# MainBoard.net
KiCad netlist of a schematic drawn in Altium Designer
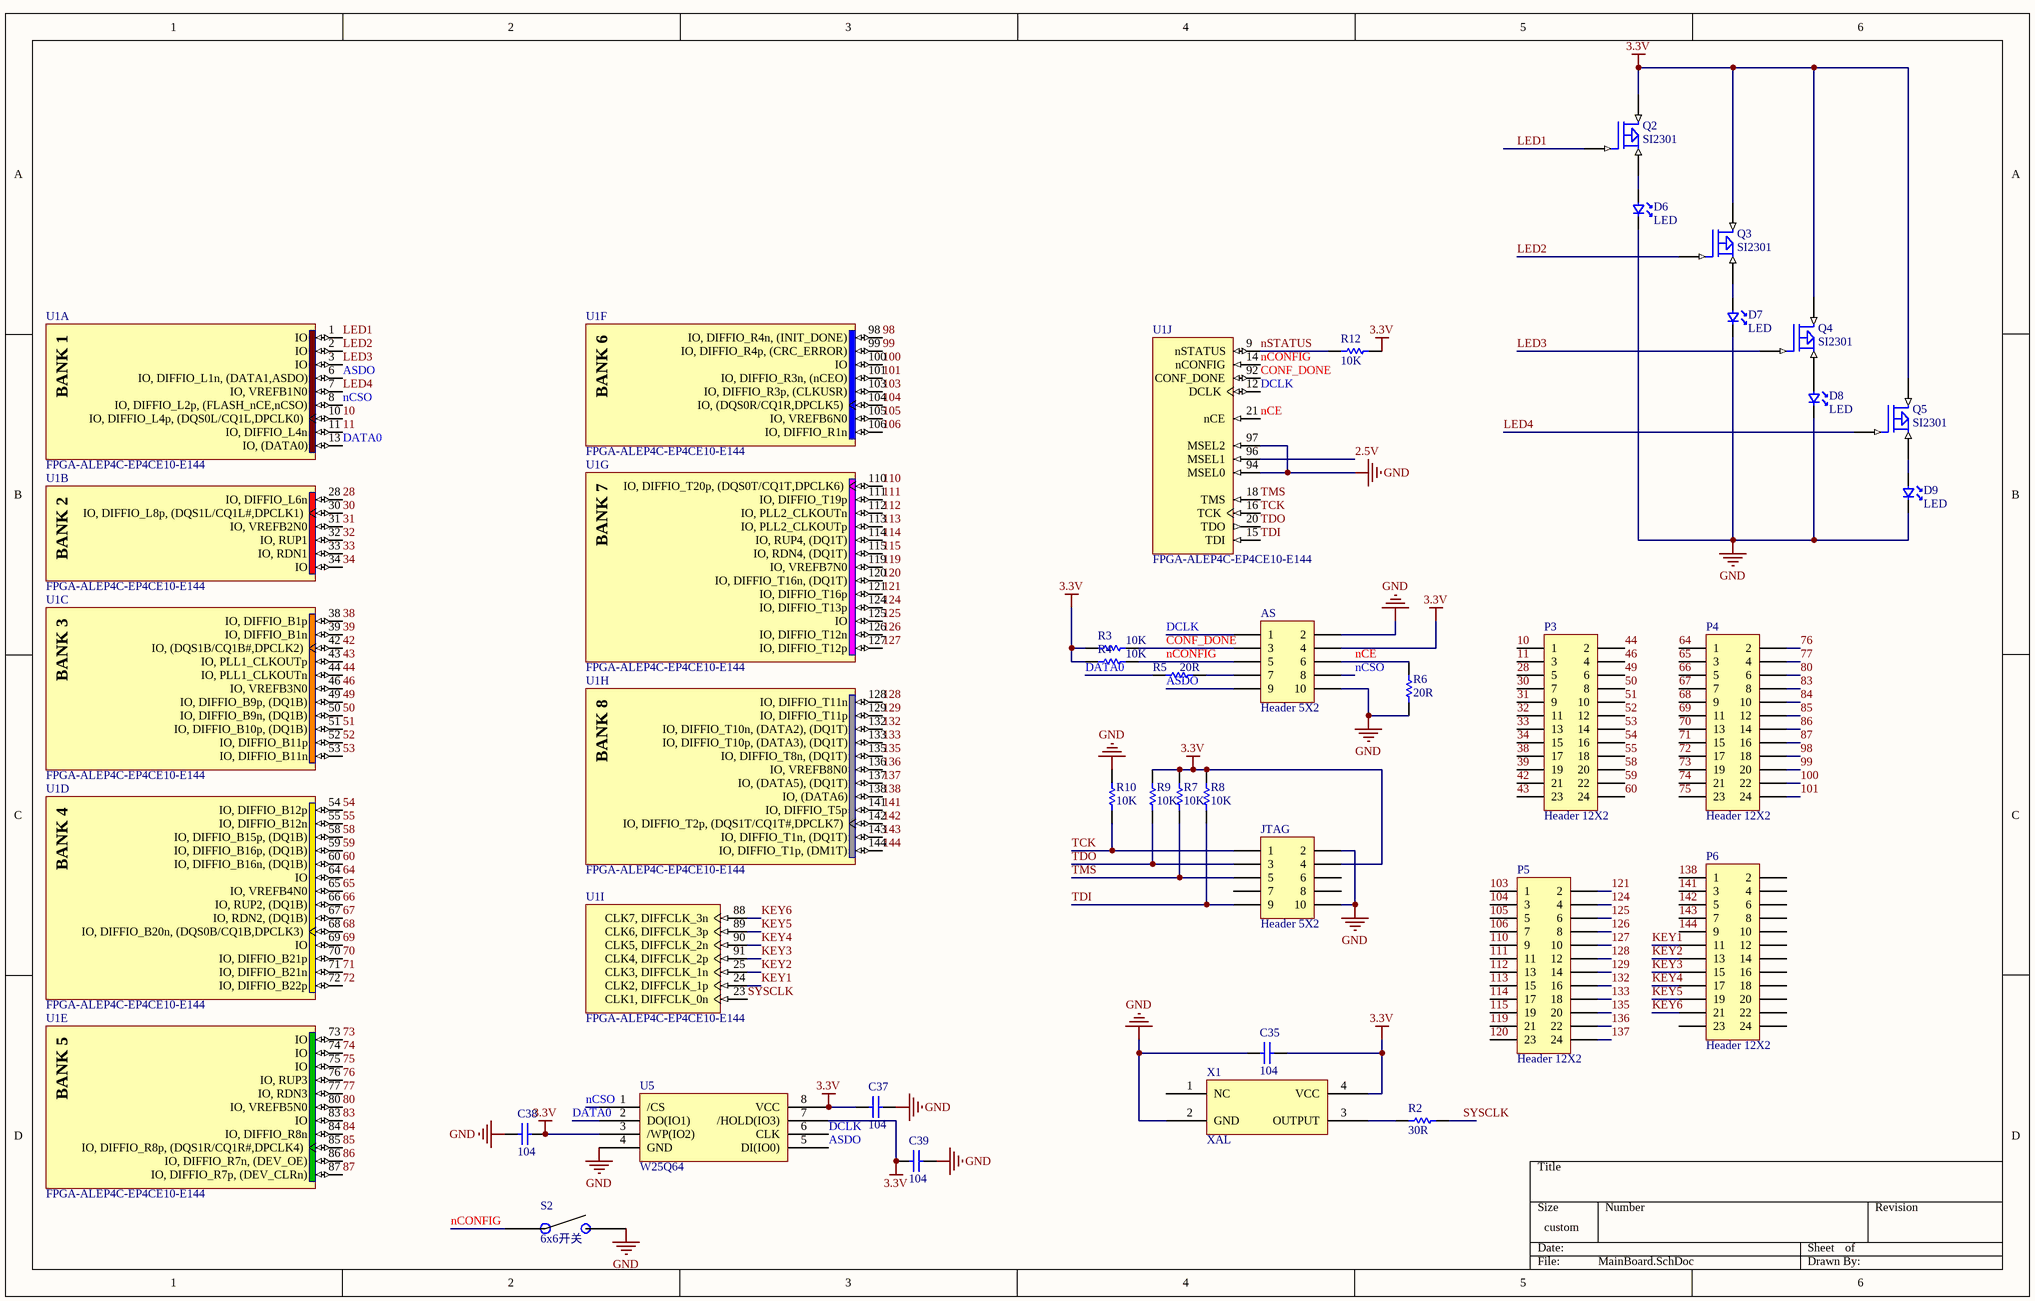
[diagram p0: MainBoard.SchDoc]

(export (version "E")
  (design (tool "Eeschema 10.0.6"))
  (components
    (comp (ref "AS")
      (value "Header 5X2")
      (footprint "HDR2X5")
      (description "Header, 5-Pin, Dual row")
      (fields (field (name "PUBLISHER") "Altium Limited"))
      (libsource (lib "Miscellaneous Connectors") (part "Header 5X2"))
    )
    (comp (ref "C35") (value "104") (footprint "0805") (libsource (lib "Schlib1") (part "Cap")))
    (comp (ref "C37") (value "104") (footprint "0805") (libsource (lib "Schlib1") (part "Cap")))
    (comp (ref "C38") (value "104") (footprint "0805") (libsource (lib "Schlib1") (part "Cap")))
    (comp (ref "C39") (value "104") (footprint "0805") (libsource (lib "Schlib1") (part "Cap")))
    (comp (ref "D6") (value "LED") (footprint "0805_s") (libsource (lib "Schlib1") (part "LED")))
    (comp (ref "D7") (value "LED") (footprint "0805_s") (libsource (lib "Schlib1") (part "LED")))
    (comp (ref "D8") (value "LED") (footprint "0805_s") (libsource (lib "Schlib1") (part "LED")))
    (comp (ref "D9") (value "LED") (footprint "0805_s") (libsource (lib "Schlib1") (part "LED")))
    (comp (ref "JTAG")
      (value "Header 5X2")
      (footprint "HDR2X5")
      (description "Header, 5-Pin, Dual row")
      (fields (field (name "PUBLISHER") "Altium Limited"))
      (libsource (lib "Miscellaneous Connectors") (part "Header 5X2"))
    )
    (comp (ref "P3")
      (value "Header 12X2")
      (footprint "HDR2X12")
      (description "Header, 12-Pin, Dual row")
      (fields (field (name "PUBLISHER") "Altium Limited"))
      (libsource (lib "Miscellaneous Connectors") (part "Header 12X2"))
    )
    (comp (ref "P4")
      (value "Header 12X2")
      (footprint "HDR2X12")
      (description "Header, 12-Pin, Dual row")
      (fields (field (name "PUBLISHER") "Altium Limited"))
      (libsource (lib "Miscellaneous Connectors") (part "Header 12X2"))
    )
    (comp (ref "P5")
      (value "Header 12X2")
      (footprint "HDR2X12")
      (description "Header, 12-Pin, Dual row")
      (fields (field (name "PUBLISHER") "Altium Limited"))
      (libsource (lib "Miscellaneous Connectors") (part "Header 12X2"))
    )
    (comp (ref "P6")
      (value "Header 12X2")
      (footprint "HDR2X12")
      (description "Header, 12-Pin, Dual row")
      (fields (field (name "PUBLISHER") "Altium Limited"))
      (libsource (lib "Miscellaneous Connectors") (part "Header 12X2"))
    )
    (comp (ref "Q2") (value "SI2301") (footprint "SOT-23") (libsource (lib "Schlib1") (part "SI2301")))
    (comp (ref "Q3") (value "SI2301") (footprint "SOT-23") (libsource (lib "Schlib1") (part "SI2301")))
    (comp (ref "Q4") (value "SI2301") (footprint "SOT-23") (libsource (lib "Schlib1") (part "SI2301")))
    (comp (ref "Q5") (value "SI2301") (footprint "SOT-23") (libsource (lib "Schlib1") (part "SI2301")))
    (comp (ref "R2") (value "30R") (footprint "0805") (libsource (lib "Schlib1") (part "Res")))
    (comp (ref "R3") (value "10K") (footprint "0805") (libsource (lib "Schlib1") (part "Res")))
    (comp (ref "R4") (value "10K") (footprint "0805") (libsource (lib "Schlib1") (part "Res")))
    (comp (ref "R5") (value "20R") (footprint "0805") (libsource (lib "Schlib1") (part "Res")))
    (comp (ref "R6") (value "20R") (footprint "0805") (libsource (lib "Schlib1") (part "Res")))
    (comp (ref "R7") (value "10K") (footprint "0805") (libsource (lib "Schlib1") (part "Res")))
    (comp (ref "R8") (value "10K") (footprint "0805") (libsource (lib "Schlib1") (part "Res")))
    (comp (ref "R9") (value "10K") (footprint "0805") (libsource (lib "Schlib1") (part "Res")))
    (comp (ref "R10") (value "10K") (footprint "0805") (libsource (lib "Schlib1") (part "Res")))
    (comp (ref "R12") (value "10K") (footprint "0805") (libsource (lib "Schlib1") (part "Res")))
    (comp (ref "S2") (value "6x6开关") (footprint "AN66") (libsource (lib "Schlib1") (part "6x6开关")))
    (comp (ref "U1")
      (value "FPGA-ALEP4C-EP4CE10-E144")
      (footprint "EQFP144_A-165_D2-54_L")
      (libsource (lib "Schlib1") (part "FPGA-ALEP4C-EP4CE10-E144"))
    )
    (comp (ref "U5")
      (value "W25Q64")
      (footprint "LC-SOIC-8_150mil")
      (libsource (lib "Schlib1") (part "W25Q64"))
    )
    (comp (ref "X1") (value "XAL") (footprint "XAL-SMD-3225_4P") (libsource (lib "Schlib1") (part "XAL")))
  )
  (nets
    (net (code "1") (name "/2.5V") (class "Default")
      (node (ref "U1") (pin "96") (pinfunction "MSEL1_96") (pintype "input"))
    )
    (net (code "2") (name "/10") (class "Default")
      (node (ref "P3") (pin "1") (pinfunction "1_1") (pintype "passive"))
      (node (ref "U1") (pin "10") (pinfunction "IO,_DIFFIO_L4p,_(DQS0L/CQ1L,DPCLK0)_10") (pintype "bidirectional"))
    )
    (net (code "3") (name "/11") (class "Default")
      (node (ref "P3") (pin "3") (pinfunction "3_3") (pintype "passive"))
      (node (ref "U1") (pin "11") (pinfunction "IO,_DIFFIO_L4n_11") (pintype "bidirectional"))
    )
    (net (code "4") (name "/28") (class "Default")
      (node (ref "P3") (pin "5") (pinfunction "5_5") (pintype "passive"))
      (node (ref "U1") (pin "28") (pinfunction "IO,_DIFFIO_L6n_28") (pintype "bidirectional"))
    )
    (net (code "5") (name "/30") (class "Default")
      (node (ref "P3") (pin "7") (pinfunction "7_7") (pintype "passive"))
      (node (ref "U1") (pin "30") (pinfunction "IO,_DIFFIO_L8p,_(DQS1L/CQ1L#,DPCLK1)_30") (pintype "bidirectional"))
    )
    (net (code "6") (name "/31") (class "Default")
      (node (ref "P3") (pin "9") (pinfunction "9_9") (pintype "passive"))
      (node (ref "U1") (pin "31") (pinfunction "IO,_VREFB2N0_31") (pintype "bidirectional"))
    )
    (net (code "7") (name "/32") (class "Default")
      (node (ref "P3") (pin "11") (pinfunction "11_11") (pintype "passive"))
      (node (ref "U1") (pin "32") (pinfunction "IO,_RUP1_32") (pintype "bidirectional"))
    )
    (net (code "8") (name "/33") (class "Default")
      (node (ref "P3") (pin "13") (pinfunction "13_13") (pintype "passive"))
      (node (ref "U1") (pin "33") (pinfunction "IO,_RDN1_33") (pintype "bidirectional"))
    )
    (net (code "9") (name "/34") (class "Default")
      (node (ref "P3") (pin "15") (pinfunction "15_15") (pintype "passive"))
      (node (ref "U1") (pin "34") (pinfunction "IO_34") (pintype "bidirectional"))
    )
    (net (code "10") (name "/38") (class "Default")
      (node (ref "P3") (pin "17") (pinfunction "17_17") (pintype "passive"))
      (node (ref "U1") (pin "38") (pinfunction "IO,_DIFFIO_B1p_38") (pintype "bidirectional"))
    )
    (net (code "11") (name "/39") (class "Default")
      (node (ref "P3") (pin "19") (pinfunction "19_19") (pintype "passive"))
      (node (ref "U1") (pin "39") (pinfunction "IO,_DIFFIO_B1n_39") (pintype "bidirectional"))
    )
    (net (code "12") (name "/42") (class "Default")
      (node (ref "P3") (pin "21") (pinfunction "21_21") (pintype "passive"))
      (node (ref "U1") (pin "42") (pinfunction "IO,_(DQS1B/CQ1B#,DPCLK2)_42") (pintype "bidirectional"))
    )
    (net (code "13") (name "/43") (class "Default")
      (node (ref "P3") (pin "23") (pinfunction "23_23") (pintype "passive"))
      (node (ref "U1") (pin "43") (pinfunction "IO,_PLL1_CLKOUTp_43") (pintype "bidirectional"))
    )
    (net (code "14") (name "/44") (class "Default")
      (node (ref "P3") (pin "2") (pinfunction "2_2") (pintype "passive"))
      (node (ref "U1") (pin "44") (pinfunction "IO,_PLL1_CLKOUTn_44") (pintype "bidirectional"))
    )
    (net (code "15") (name "/46") (class "Default")
      (node (ref "P3") (pin "4") (pinfunction "4_4") (pintype "passive"))
      (node (ref "U1") (pin "46") (pinfunction "IO,_VREFB3N0_46") (pintype "bidirectional"))
    )
    (net (code "16") (name "/49") (class "Default")
      (node (ref "P3") (pin "6") (pinfunction "6_6") (pintype "passive"))
      (node (ref "U1") (pin "49") (pinfunction "IO,_DIFFIO_B9p,_(DQ1B)_49") (pintype "bidirectional"))
    )
    (net (code "17") (name "/50") (class "Default")
      (node (ref "P3") (pin "8") (pinfunction "8_8") (pintype "passive"))
      (node (ref "U1") (pin "50") (pinfunction "IO,_DIFFIO_B9n,_(DQ1B)_50") (pintype "bidirectional"))
    )
    (net (code "18") (name "/51") (class "Default")
      (node (ref "P3") (pin "10") (pinfunction "10_10") (pintype "passive"))
      (node (ref "U1") (pin "51") (pinfunction "IO,_DIFFIO_B10p,_(DQ1B)_51") (pintype "bidirectional"))
    )
    (net (code "19") (name "/52") (class "Default")
      (node (ref "P3") (pin "12") (pinfunction "12_12") (pintype "passive"))
      (node (ref "U1") (pin "52") (pinfunction "IO,_DIFFIO_B11p_52") (pintype "bidirectional"))
    )
    (net (code "20") (name "/53") (class "Default")
      (node (ref "P3") (pin "14") (pinfunction "14_14") (pintype "passive"))
      (node (ref "U1") (pin "53") (pinfunction "IO,_DIFFIO_B11n_53") (pintype "bidirectional"))
    )
    (net (code "21") (name "/54") (class "Default")
      (node (ref "P3") (pin "16") (pinfunction "16_16") (pintype "passive"))
      (node (ref "U1") (pin "54") (pinfunction "IO,_DIFFIO_B12p_54") (pintype "bidirectional"))
    )
    (net (code "22") (name "/55") (class "Default")
      (node (ref "P3") (pin "18") (pinfunction "18_18") (pintype "passive"))
      (node (ref "U1") (pin "55") (pinfunction "IO,_DIFFIO_B12n_55") (pintype "bidirectional"))
    )
    (net (code "23") (name "/58") (class "Default")
      (node (ref "P3") (pin "20") (pinfunction "20_20") (pintype "passive"))
      (node (ref "U1") (pin "58") (pinfunction "IO,_DIFFIO_B15p,_(DQ1B)_58") (pintype "bidirectional"))
    )
    (net (code "24") (name "/59") (class "Default")
      (node (ref "P3") (pin "22") (pinfunction "22_22") (pintype "passive"))
      (node (ref "U1") (pin "59") (pinfunction "IO,_DIFFIO_B16p,_(DQ1B)_59") (pintype "bidirectional"))
    )
    (net (code "25") (name "/60") (class "Default")
      (node (ref "P3") (pin "24") (pinfunction "24_24") (pintype "passive"))
      (node (ref "U1") (pin "60") (pinfunction "IO,_DIFFIO_B16n,_(DQ1B)_60") (pintype "bidirectional"))
    )
    (net (code "26") (name "/64") (class "Default")
      (node (ref "P4") (pin "1") (pinfunction "1_1") (pintype "passive"))
      (node (ref "U1") (pin "64") (pinfunction "IO_64") (pintype "bidirectional"))
    )
    (net (code "27") (name "/65") (class "Default")
      (node (ref "P4") (pin "3") (pinfunction "3_3") (pintype "passive"))
      (node (ref "U1") (pin "65") (pinfunction "IO,_VREFB4N0_65") (pintype "bidirectional"))
    )
    (net (code "28") (name "/66") (class "Default")
      (node (ref "P4") (pin "5") (pinfunction "5_5") (pintype "passive"))
      (node (ref "U1") (pin "66") (pinfunction "IO,_RUP2,_(DQ1B)_66") (pintype "bidirectional"))
    )
    (net (code "29") (name "/67") (class "Default")
      (node (ref "P4") (pin "7") (pinfunction "7_7") (pintype "passive"))
      (node (ref "U1") (pin "67") (pinfunction "IO,_RDN2,_(DQ1B)_67") (pintype "bidirectional"))
    )
    (net (code "30") (name "/68") (class "Default")
      (node (ref "P4") (pin "9") (pinfunction "9_9") (pintype "passive"))
      (node (ref "U1") (pin "68") (pinfunction "IO,_DIFFIO_B20n,_(DQS0B/CQ1B,DPCLK3)_68") (pintype "bidirectional"))
    )
    (net (code "31") (name "/69") (class "Default")
      (node (ref "P4") (pin "11") (pinfunction "11_11") (pintype "passive"))
      (node (ref "U1") (pin "69") (pinfunction "IO_69") (pintype "bidirectional"))
    )
    (net (code "32") (name "/70") (class "Default")
      (node (ref "P4") (pin "13") (pinfunction "13_13") (pintype "passive"))
      (node (ref "U1") (pin "70") (pinfunction "IO,_DIFFIO_B21p_70") (pintype "bidirectional"))
    )
    (net (code "33") (name "/71") (class "Default")
      (node (ref "P4") (pin "15") (pinfunction "15_15") (pintype "passive"))
      (node (ref "U1") (pin "71") (pinfunction "IO,_DIFFIO_B21n_71") (pintype "bidirectional"))
    )
    (net (code "34") (name "/72") (class "Default")
      (node (ref "P4") (pin "17") (pinfunction "17_17") (pintype "passive"))
      (node (ref "U1") (pin "72") (pinfunction "IO,_DIFFIO_B22p_72") (pintype "bidirectional"))
    )
    (net (code "35") (name "/73") (class "Default")
      (node (ref "P4") (pin "19") (pinfunction "19_19") (pintype "passive"))
      (node (ref "U1") (pin "73") (pinfunction "IO_73") (pintype "bidirectional"))
    )
    (net (code "36") (name "/74") (class "Default")
      (node (ref "P4") (pin "21") (pinfunction "21_21") (pintype "passive"))
      (node (ref "U1") (pin "74") (pinfunction "IO_74") (pintype "bidirectional"))
    )
    (net (code "37") (name "/75") (class "Default")
      (node (ref "P4") (pin "23") (pinfunction "23_23") (pintype "passive"))
      (node (ref "U1") (pin "75") (pinfunction "IO_75") (pintype "bidirectional"))
    )
    (net (code "38") (name "/76") (class "Default")
      (node (ref "P4") (pin "2") (pinfunction "2_2") (pintype "passive"))
      (node (ref "U1") (pin "76") (pinfunction "IO,_RUP3_76") (pintype "bidirectional"))
    )
    (net (code "39") (name "/77") (class "Default")
      (node (ref "P4") (pin "4") (pinfunction "4_4") (pintype "passive"))
      (node (ref "U1") (pin "77") (pinfunction "IO,_RDN3_77") (pintype "bidirectional"))
    )
    (net (code "40") (name "/80") (class "Default")
      (node (ref "P4") (pin "6") (pinfunction "6_6") (pintype "passive"))
      (node (ref "U1") (pin "80") (pinfunction "IO,_VREFB5N0_80") (pintype "bidirectional"))
    )
    (net (code "41") (name "/83") (class "Default")
      (node (ref "P4") (pin "8") (pinfunction "8_8") (pintype "passive"))
      (node (ref "U1") (pin "83") (pinfunction "IO_83") (pintype "bidirectional"))
    )
    (net (code "42") (name "/84") (class "Default")
      (node (ref "P4") (pin "10") (pinfunction "10_10") (pintype "passive"))
      (node (ref "U1") (pin "84") (pinfunction "IO,_DIFFIO_R8n_84") (pintype "bidirectional"))
    )
    (net (code "43") (name "/85") (class "Default")
      (node (ref "P4") (pin "12") (pinfunction "12_12") (pintype "passive"))
      (node (ref "U1") (pin "85") (pinfunction "IO,_DIFFIO_R8p,_(DQS1R/CQ1R#,DPCLK4)_85") (pintype "bidirectional"))
    )
    (net (code "44") (name "/86") (class "Default")
      (node (ref "P4") (pin "14") (pinfunction "14_14") (pintype "passive"))
      (node (ref "U1") (pin "86") (pinfunction "IO,_DIFFIO_R7n,_(DEV_OE)_86") (pintype "bidirectional"))
    )
    (net (code "45") (name "/87") (class "Default")
      (node (ref "P4") (pin "16") (pinfunction "16_16") (pintype "passive"))
      (node (ref "U1") (pin "87") (pinfunction "IO,_DIFFIO_R7p,_(DEV_CLRn)_87") (pintype "bidirectional"))
    )
    (net (code "46") (name "/98") (class "Default")
      (node (ref "P4") (pin "18") (pinfunction "18_18") (pintype "passive"))
      (node (ref "U1") (pin "98") (pinfunction "IO,_DIFFIO_R4n,_(INIT_DONE)_98") (pintype "bidirectional"))
    )
    (net (code "47") (name "/99") (class "Default")
      (node (ref "P4") (pin "20") (pinfunction "20_20") (pintype "passive"))
      (node (ref "U1") (pin "99") (pinfunction "IO,_DIFFIO_R4p,_(CRC_ERROR)_99") (pintype "bidirectional"))
    )
    (net (code "48") (name "/100") (class "Default")
      (node (ref "P4") (pin "22") (pinfunction "22_22") (pintype "passive"))
      (node (ref "U1") (pin "100") (pinfunction "IO_100") (pintype "bidirectional"))
    )
    (net (code "49") (name "/101") (class "Default")
      (node (ref "P4") (pin "24") (pinfunction "24_24") (pintype "passive"))
      (node (ref "U1") (pin "101") (pinfunction "IO,_DIFFIO_R3n,_(nCEO)_101") (pintype "bidirectional"))
    )
    (net (code "50") (name "/103") (class "Default")
      (node (ref "P5") (pin "1") (pinfunction "1_1") (pintype "passive"))
      (node (ref "U1") (pin "103") (pinfunction "IO,_DIFFIO_R3p,_(CLKUSR)_103") (pintype "bidirectional"))
    )
    (net (code "51") (name "/104") (class "Default")
      (node (ref "P5") (pin "3") (pinfunction "3_3") (pintype "passive"))
      (node (ref "U1") (pin "104") (pinfunction "IO,_(DQS0R/CQ1R,DPCLK5)_104") (pintype "bidirectional"))
    )
    (net (code "52") (name "/105") (class "Default")
      (node (ref "P5") (pin "5") (pinfunction "5_5") (pintype "passive"))
      (node (ref "U1") (pin "105") (pinfunction "IO,_VREFB6N0_105") (pintype "bidirectional"))
    )
    (net (code "53") (name "/106") (class "Default")
      (node (ref "P5") (pin "7") (pinfunction "7_7") (pintype "passive"))
      (node (ref "U1") (pin "106") (pinfunction "IO,_DIFFIO_R1n_106") (pintype "bidirectional"))
    )
    (net (code "54") (name "/110") (class "Default")
      (node (ref "P5") (pin "9") (pinfunction "9_9") (pintype "passive"))
      (node (ref "U1") (pin "110") (pinfunction "IO,_DIFFIO_T20p,_(DQS0T/CQ1T,DPCLK6)_110") (pintype "bidirectional"))
    )
    (net (code "55") (name "/111") (class "Default")
      (node (ref "P5") (pin "11") (pinfunction "11_11") (pintype "passive"))
      (node (ref "U1") (pin "111") (pinfunction "IO,_DIFFIO_T19p_111") (pintype "bidirectional"))
    )
    (net (code "56") (name "/112") (class "Default")
      (node (ref "P5") (pin "13") (pinfunction "13_13") (pintype "passive"))
      (node (ref "U1") (pin "112") (pinfunction "IO,_PLL2_CLKOUTn_112") (pintype "bidirectional"))
    )
    (net (code "57") (name "/113") (class "Default")
      (node (ref "P5") (pin "15") (pinfunction "15_15") (pintype "passive"))
      (node (ref "U1") (pin "113") (pinfunction "IO,_PLL2_CLKOUTp_113") (pintype "bidirectional"))
    )
    (net (code "58") (name "/114") (class "Default")
      (node (ref "P5") (pin "17") (pinfunction "17_17") (pintype "passive"))
      (node (ref "U1") (pin "114") (pinfunction "IO,_RUP4,_(DQ1T)_114") (pintype "bidirectional"))
    )
    (net (code "59") (name "/115") (class "Default")
      (node (ref "P5") (pin "19") (pinfunction "19_19") (pintype "passive"))
      (node (ref "U1") (pin "115") (pinfunction "IO,_RDN4,_(DQ1T)_115") (pintype "bidirectional"))
    )
    (net (code "60") (name "/119") (class "Default")
      (node (ref "P5") (pin "21") (pinfunction "21_21") (pintype "passive"))
      (node (ref "U1") (pin "119") (pinfunction "IO,_VREFB7N0_119") (pintype "bidirectional"))
    )
    (net (code "61") (name "/120") (class "Default")
      (node (ref "P5") (pin "23") (pinfunction "23_23") (pintype "passive"))
      (node (ref "U1") (pin "120") (pinfunction "IO,_DIFFIO_T16n,_(DQ1T)_120") (pintype "bidirectional"))
    )
    (net (code "62") (name "/121") (class "Default")
      (node (ref "P5") (pin "2") (pinfunction "2_2") (pintype "passive"))
      (node (ref "U1") (pin "121") (pinfunction "IO,_DIFFIO_T16p_121") (pintype "bidirectional"))
    )
    (net (code "63") (name "/124") (class "Default")
      (node (ref "P5") (pin "4") (pinfunction "4_4") (pintype "passive"))
      (node (ref "U1") (pin "124") (pinfunction "IO,_DIFFIO_T13p_124") (pintype "bidirectional"))
    )
    (net (code "64") (name "/125") (class "Default")
      (node (ref "P5") (pin "6") (pinfunction "6_6") (pintype "passive"))
      (node (ref "U1") (pin "125") (pinfunction "IO_125") (pintype "bidirectional"))
    )
    (net (code "65") (name "/126") (class "Default")
      (node (ref "P5") (pin "8") (pinfunction "8_8") (pintype "passive"))
      (node (ref "U1") (pin "126") (pinfunction "IO,_DIFFIO_T12n_126") (pintype "bidirectional"))
    )
    (net (code "66") (name "/127") (class "Default")
      (node (ref "P5") (pin "10") (pinfunction "10_10") (pintype "passive"))
      (node (ref "U1") (pin "127") (pinfunction "IO,_DIFFIO_T12p_127") (pintype "bidirectional"))
    )
    (net (code "67") (name "/128") (class "Default")
      (node (ref "P5") (pin "12") (pinfunction "12_12") (pintype "passive"))
      (node (ref "U1") (pin "128") (pinfunction "IO,_DIFFIO_T11n_128") (pintype "bidirectional"))
    )
    (net (code "68") (name "/129") (class "Default")
      (node (ref "P5") (pin "14") (pinfunction "14_14") (pintype "passive"))
      (node (ref "U1") (pin "129") (pinfunction "IO,_DIFFIO_T11p_129") (pintype "bidirectional"))
    )
    (net (code "69") (name "/132") (class "Default")
      (node (ref "P5") (pin "16") (pinfunction "16_16") (pintype "passive"))
      (node (ref "U1") (pin "132") (pinfunction "IO,_DIFFIO_T10n,_(DATA2),_(DQ1T)_132") (pintype "bidirectional"))
    )
    (net (code "70") (name "/133") (class "Default")
      (node (ref "P5") (pin "18") (pinfunction "18_18") (pintype "passive"))
      (node (ref "U1") (pin "133") (pinfunction "IO,_DIFFIO_T10p,_(DATA3),_(DQ1T)_133") (pintype "bidirectional"))
    )
    (net (code "71") (name "/135") (class "Default")
      (node (ref "P5") (pin "20") (pinfunction "20_20") (pintype "passive"))
      (node (ref "U1") (pin "135") (pinfunction "IO,_DIFFIO_T8n,_(DQ1T)_135") (pintype "bidirectional"))
    )
    (net (code "72") (name "/136") (class "Default")
      (node (ref "P5") (pin "22") (pinfunction "22_22") (pintype "passive"))
      (node (ref "U1") (pin "136") (pinfunction "IO,_VREFB8N0_136") (pintype "bidirectional"))
    )
    (net (code "73") (name "/137") (class "Default")
      (node (ref "P5") (pin "24") (pinfunction "24_24") (pintype "passive"))
      (node (ref "U1") (pin "137") (pinfunction "IO,_(DATA5),_(DQ1T)_137") (pintype "bidirectional"))
    )
    (net (code "74") (name "/138") (class "Default")
      (node (ref "P6") (pin "1") (pinfunction "1_1") (pintype "passive"))
      (node (ref "U1") (pin "138") (pinfunction "IO,_(DATA6)_138") (pintype "bidirectional"))
    )
    (net (code "75") (name "/141") (class "Default")
      (node (ref "P6") (pin "3") (pinfunction "3_3") (pintype "passive"))
      (node (ref "U1") (pin "141") (pinfunction "IO,_DIFFIO_T5p_141") (pintype "bidirectional"))
    )
    (net (code "76") (name "/142") (class "Default")
      (node (ref "P6") (pin "5") (pinfunction "5_5") (pintype "passive"))
      (node (ref "U1") (pin "142") (pinfunction "IO,_DIFFIO_T2p,_(DQS1T/CQ1T#,DPCLK7)_142") (pintype "bidirectional"))
    )
    (net (code "77") (name "/143") (class "Default")
      (node (ref "P6") (pin "7") (pinfunction "7_7") (pintype "passive"))
      (node (ref "U1") (pin "143") (pinfunction "IO,_DIFFIO_T1n,_(DQ1T)_143") (pintype "bidirectional"))
    )
    (net (code "78") (name "/144") (class "Default")
      (node (ref "P6") (pin "9") (pinfunction "9_9") (pintype "passive"))
      (node (ref "U1") (pin "144") (pinfunction "IO,_DIFFIO_T1p,_(DM1T)_144") (pintype "bidirectional"))
    )
    (net (code "79") (name "/ASDO") (class "Default")
      (node (ref "AS") (pin "9") (pinfunction "9_9") (pintype "passive"))
      (node (ref "U1") (pin "6") (pinfunction "IO,_DIFFIO_L1n,_(DATA1,ASDO)_6") (pintype "bidirectional"))
      (node (ref "U5") (pin "5") (pinfunction "DI(IO0)_5") (pintype "passive"))
    )
    (net (code "80") (name "/CONF_DONE") (class "Default")
      (node (ref "AS") (pin "3") (pinfunction "3_3") (pintype "passive"))
      (node (ref "R3") (pin "2") (pinfunction "2_2") (pintype "passive"))
      (node (ref "U1") (pin "92") (pinfunction "CONF_DONE_92") (pintype "bidirectional"))
    )
    (net (code "81") (name "/DATA0") (class "Default")
      (node (ref "R5") (pin "1") (pinfunction "1_1") (pintype "passive"))
      (node (ref "U1") (pin "13") (pinfunction "IO,_(DATA0)_13") (pintype "bidirectional"))
      (node (ref "U5") (pin "2") (pinfunction "DO(IO1)_2") (pintype "passive"))
    )
    (net (code "82") (name "/DCLK") (class "Default")
      (node (ref "AS") (pin "1") (pinfunction "1_1") (pintype "passive"))
      (node (ref "U1") (pin "12") (pinfunction "DCLK_12") (pintype "bidirectional"))
      (node (ref "U5") (pin "6") (pinfunction "CLK_6") (pintype "passive"))
    )
    (net (code "83") (name "/KEY1") (class "Default")
      (node (ref "P6") (pin "11") (pinfunction "11_11") (pintype "passive"))
      (node (ref "U1") (pin "24") (pinfunction "CLK2,_DIFFCLK_1p_24") (pintype "input"))
    )
    (net (code "84") (name "/KEY2") (class "Default")
      (node (ref "P6") (pin "13") (pinfunction "13_13") (pintype "passive"))
      (node (ref "U1") (pin "25") (pinfunction "CLK3,_DIFFCLK_1n_25") (pintype "input"))
    )
    (net (code "85") (name "/KEY3") (class "Default")
      (node (ref "P6") (pin "15") (pinfunction "15_15") (pintype "passive"))
      (node (ref "U1") (pin "91") (pinfunction "CLK4,_DIFFCLK_2p_91") (pintype "input"))
    )
    (net (code "86") (name "/KEY4") (class "Default")
      (node (ref "P6") (pin "17") (pinfunction "17_17") (pintype "passive"))
      (node (ref "U1") (pin "90") (pinfunction "CLK5,_DIFFCLK_2n_90") (pintype "input"))
    )
    (net (code "87") (name "/KEY5") (class "Default")
      (node (ref "P6") (pin "19") (pinfunction "19_19") (pintype "passive"))
      (node (ref "U1") (pin "89") (pinfunction "CLK6,_DIFFCLK_3p_89") (pintype "input"))
    )
    (net (code "88") (name "/KEY6") (class "Default")
      (node (ref "P6") (pin "21") (pinfunction "21_21") (pintype "passive"))
      (node (ref "U1") (pin "88") (pinfunction "CLK7,_DIFFCLK_3n_88") (pintype "input"))
    )
    (net (code "89") (name "/LED1") (class "Default")
      (node (ref "Q2") (pin "1") (pinfunction "G_1") (pintype "input"))
      (node (ref "U1") (pin "1") (pinfunction "IO_1") (pintype "bidirectional"))
    )
    (net (code "90") (name "/LED2") (class "Default")
      (node (ref "Q3") (pin "1") (pinfunction "G_1") (pintype "input"))
      (node (ref "U1") (pin "2") (pinfunction "IO_2") (pintype "bidirectional"))
    )
    (net (code "91") (name "/LED3") (class "Default")
      (node (ref "Q4") (pin "1") (pinfunction "G_1") (pintype "input"))
      (node (ref "U1") (pin "3") (pinfunction "IO_3") (pintype "bidirectional"))
    )
    (net (code "92") (name "/LED4") (class "Default")
      (node (ref "Q5") (pin "1") (pinfunction "G_1") (pintype "input"))
      (node (ref "U1") (pin "7") (pinfunction "IO,_VREFB1N0_7") (pintype "bidirectional"))
    )
    (net (code "93") (name "/SYSCLK") (class "Default")
      (node (ref "R2") (pin "2") (pinfunction "2_2") (pintype "passive"))
      (node (ref "U1") (pin "23") (pinfunction "CLK1,_DIFFCLK_0n_23") (pintype "input"))
    )
    (net (code "94") (name "/TCK") (class "Default")
      (node (ref "JTAG") (pin "1") (pinfunction "1_1") (pintype "passive"))
      (node (ref "R10") (pin "1") (pinfunction "1_1") (pintype "passive"))
      (node (ref "U1") (pin "16") (pinfunction "TCK_16") (pintype "input"))
    )
    (net (code "95") (name "/TDI") (class "Default")
      (node (ref "JTAG") (pin "9") (pinfunction "9_9") (pintype "passive"))
      (node (ref "R8") (pin "1") (pinfunction "1_1") (pintype "passive"))
      (node (ref "U1") (pin "15") (pinfunction "TDI_15") (pintype "input"))
    )
    (net (code "96") (name "/TDO") (class "Default")
      (node (ref "JTAG") (pin "3") (pinfunction "3_3") (pintype "passive"))
      (node (ref "R9") (pin "1") (pinfunction "1_1") (pintype "passive"))
      (node (ref "U1") (pin "20") (pinfunction "TDO_20") (pintype "output"))
    )
    (net (code "97") (name "/TMS") (class "Default")
      (node (ref "JTAG") (pin "5") (pinfunction "5_5") (pintype "passive"))
      (node (ref "R7") (pin "1") (pinfunction "1_1") (pintype "passive"))
      (node (ref "U1") (pin "18") (pinfunction "TMS_18") (pintype "input"))
    )
    (net (code "98") (name "/nCE") (class "Default")
      (node (ref "AS") (pin "6") (pinfunction "6_6") (pintype "passive"))
      (node (ref "R6") (pin "2") (pinfunction "2_2") (pintype "passive"))
      (node (ref "U1") (pin "21") (pinfunction "nCE_21") (pintype "input"))
    )
    (net (code "99") (name "/nCONFIG") (class "Default")
      (node (ref "AS") (pin "5") (pinfunction "5_5") (pintype "passive"))
      (node (ref "R4") (pin "2") (pinfunction "2_2") (pintype "passive"))
      (node (ref "S2") (pin "2") (pinfunction "2_2") (pintype "passive"))
      (node (ref "U1") (pin "14") (pinfunction "nCONFIG_14") (pintype "input"))
    )
    (net (code "100") (name "/nCSO") (class "Default")
      (node (ref "AS") (pin "8") (pinfunction "8_8") (pintype "passive"))
      (node (ref "U1") (pin "8") (pinfunction "IO,_DIFFIO_L2p,_(FLASH_nCE,nCSO)_8") (pintype "bidirectional"))
      (node (ref "U5") (pin "1") (pinfunction "/CS_1") (pintype "passive"))
    )
    (net (code "101") (name "/nSTATUS") (class "Default")
      (node (ref "R12") (pin "1") (pinfunction "1_1") (pintype "passive"))
      (node (ref "U1") (pin "9") (pinfunction "nSTATUS_9") (pintype "bidirectional"))
    )
    (net (code "102") (name "3.3V") (class "Default")
      (node (ref "AS") (pin "4") (pinfunction "4_4") (pintype "passive"))
      (node (ref "C35") (pin "2") (pinfunction "2_2") (pintype "passive"))
      (node (ref "C37") (pin "1") (pinfunction "1_1") (pintype "passive"))
      (node (ref "C38") (pin "2") (pinfunction "2_2") (pintype "passive"))
      (node (ref "C39") (pin "1") (pinfunction "1_1") (pintype "passive"))
      (node (ref "JTAG") (pin "4") (pinfunction "4_4") (pintype "passive"))
      (node (ref "Q2") (pin "2") (pinfunction "S_2") (pintype "input"))
      (node (ref "Q3") (pin "2") (pinfunction "S_2") (pintype "input"))
      (node (ref "Q4") (pin "2") (pinfunction "S_2") (pintype "input"))
      (node (ref "Q5") (pin "2") (pinfunction "S_2") (pintype "input"))
      (node (ref "R12") (pin "2") (pinfunction "2_2") (pintype "passive"))
      (node (ref "R3") (pin "1") (pinfunction "1_1") (pintype "passive"))
      (node (ref "R4") (pin "1") (pinfunction "1_1") (pintype "passive"))
      (node (ref "R7") (pin "2") (pinfunction "2_2") (pintype "passive"))
      (node (ref "R8") (pin "2") (pinfunction "2_2") (pintype "passive"))
      (node (ref "R9") (pin "2") (pinfunction "2_2") (pintype "passive"))
      (node (ref "U5") (pin "3") (pinfunction "/WP(IO2)_3") (pintype "passive"))
      (node (ref "U5") (pin "7") (pinfunction "/HOLD(IO3)_7") (pintype "passive"))
      (node (ref "U5") (pin "8") (pinfunction "VCC_8") (pintype "passive"))
      (node (ref "X1") (pin "4") (pinfunction "VCC_4") (pintype "passive"))
    )
    (net (code "103") (name "GND") (class "Default")
      (node (ref "AS") (pin "10") (pinfunction "10_10") (pintype "passive"))
      (node (ref "AS") (pin "2") (pinfunction "2_2") (pintype "passive"))
      (node (ref "C35") (pin "1") (pinfunction "1_1") (pintype "passive"))
      (node (ref "C37") (pin "2") (pinfunction "2_2") (pintype "passive"))
      (node (ref "C38") (pin "1") (pinfunction "1_1") (pintype "passive"))
      (node (ref "C39") (pin "2") (pinfunction "2_2") (pintype "passive"))
      (node (ref "D6") (pin "1") (pinfunction "1_1") (pintype "passive"))
      (node (ref "D7") (pin "1") (pinfunction "1_1") (pintype "passive"))
      (node (ref "D8") (pin "1") (pinfunction "1_1") (pintype "passive"))
      (node (ref "D9") (pin "1") (pinfunction "1_1") (pintype "passive"))
      (node (ref "JTAG") (pin "10") (pinfunction "10_10") (pintype "passive"))
      (node (ref "JTAG") (pin "2") (pinfunction "2_2") (pintype "passive"))
      (node (ref "R10") (pin "2") (pinfunction "2_2") (pintype "passive"))
      (node (ref "R6") (pin "1") (pinfunction "1_1") (pintype "passive"))
      (node (ref "S2") (pin "1") (pinfunction "1_1") (pintype "passive"))
      (node (ref "U1") (pin "94") (pinfunction "MSEL0_94") (pintype "input"))
      (node (ref "U1") (pin "97") (pinfunction "MSEL2_97") (pintype "input"))
      (node (ref "U5") (pin "4") (pinfunction "GND_4") (pintype "passive"))
      (node (ref "X1") (pin "2") (pinfunction "GND_2") (pintype "passive"))
    )
    (net (code "104") (name "Net-(AS-Pad7)") (class "Default")
      (node (ref "AS") (pin "7") (pinfunction "7_7") (pintype "passive"))
      (node (ref "R5") (pin "2") (pinfunction "2_2") (pintype "passive"))
    )
    (net (code "105") (name "Net-(Q2-D)") (class "Default")
      (node (ref "D6") (pin "2") (pinfunction "2_2") (pintype "passive"))
      (node (ref "Q2") (pin "3") (pinfunction "D_3") (pintype "input"))
    )
    (net (code "106") (name "Net-(Q3-D)") (class "Default")
      (node (ref "D7") (pin "2") (pinfunction "2_2") (pintype "passive"))
      (node (ref "Q3") (pin "3") (pinfunction "D_3") (pintype "input"))
    )
    (net (code "107") (name "Net-(Q4-D)") (class "Default")
      (node (ref "D8") (pin "2") (pinfunction "2_2") (pintype "passive"))
      (node (ref "Q4") (pin "3") (pinfunction "D_3") (pintype "input"))
    )
    (net (code "108") (name "Net-(Q5-D)") (class "Default")
      (node (ref "D9") (pin "2") (pinfunction "2_2") (pintype "passive"))
      (node (ref "Q5") (pin "3") (pinfunction "D_3") (pintype "input"))
    )
    (net (code "109") (name "Net-(X1-OUTPUT)") (class "Default")
      (node (ref "R2") (pin "1") (pinfunction "1_1") (pintype "passive"))
      (node (ref "X1") (pin "3") (pinfunction "OUTPUT_3") (pintype "passive"))
    )
    (net (code "110") (name "unconnected-(JTAG-Pad6)") (class "Default")
      (node (ref "JTAG") (pin "6") (pinfunction "6_6") (pintype "passive"))
    )
    (net (code "111") (name "unconnected-(JTAG-Pad7)") (class "Default")
      (node (ref "JTAG") (pin "7") (pinfunction "7_7") (pintype "passive"))
    )
    (net (code "112") (name "unconnected-(JTAG-Pad8)") (class "Default")
      (node (ref "JTAG") (pin "8") (pinfunction "8_8") (pintype "passive"))
    )
    (net (code "113") (name "unconnected-(P6-Pad2)") (class "Default")
      (node (ref "P6") (pin "2") (pinfunction "2_2") (pintype "passive"))
    )
    (net (code "114") (name "unconnected-(P6-Pad4)") (class "Default")
      (node (ref "P6") (pin "4") (pinfunction "4_4") (pintype "passive"))
    )
    (net (code "115") (name "unconnected-(P6-Pad6)") (class "Default")
      (node (ref "P6") (pin "6") (pinfunction "6_6") (pintype "passive"))
    )
    (net (code "116") (name "unconnected-(P6-Pad8)") (class "Default")
      (node (ref "P6") (pin "8") (pinfunction "8_8") (pintype "passive"))
    )
    (net (code "117") (name "unconnected-(P6-Pad10)") (class "Default")
      (node (ref "P6") (pin "10") (pinfunction "10_10") (pintype "passive"))
    )
    (net (code "118") (name "unconnected-(P6-Pad12)") (class "Default")
      (node (ref "P6") (pin "12") (pinfunction "12_12") (pintype "passive"))
    )
    (net (code "119") (name "unconnected-(P6-Pad14)") (class "Default")
      (node (ref "P6") (pin "14") (pinfunction "14_14") (pintype "passive"))
    )
    (net (code "120") (name "unconnected-(P6-Pad16)") (class "Default")
      (node (ref "P6") (pin "16") (pinfunction "16_16") (pintype "passive"))
    )
    (net (code "121") (name "unconnected-(P6-Pad18)") (class "Default")
      (node (ref "P6") (pin "18") (pinfunction "18_18") (pintype "passive"))
    )
    (net (code "122") (name "unconnected-(P6-Pad20)") (class "Default")
      (node (ref "P6") (pin "20") (pinfunction "20_20") (pintype "passive"))
    )
    (net (code "123") (name "unconnected-(P6-Pad22)") (class "Default")
      (node (ref "P6") (pin "22") (pinfunction "22_22") (pintype "passive"))
    )
    (net (code "124") (name "unconnected-(P6-Pad23)") (class "Default")
      (node (ref "P6") (pin "23") (pinfunction "23_23") (pintype "passive"))
    )
    (net (code "125") (name "unconnected-(P6-Pad24)") (class "Default")
      (node (ref "P6") (pin "24") (pinfunction "24_24") (pintype "passive"))
    )
    (net (code "126") (name "unconnected-(X1-NC-Pad1)") (class "Default")
      (node (ref "X1") (pin "1") (pinfunction "NC_1") (pintype "passive"))
    )
  )
)
